# RFIDLockSCH.net
KiCad netlist of a schematic drawn in Altium Designer
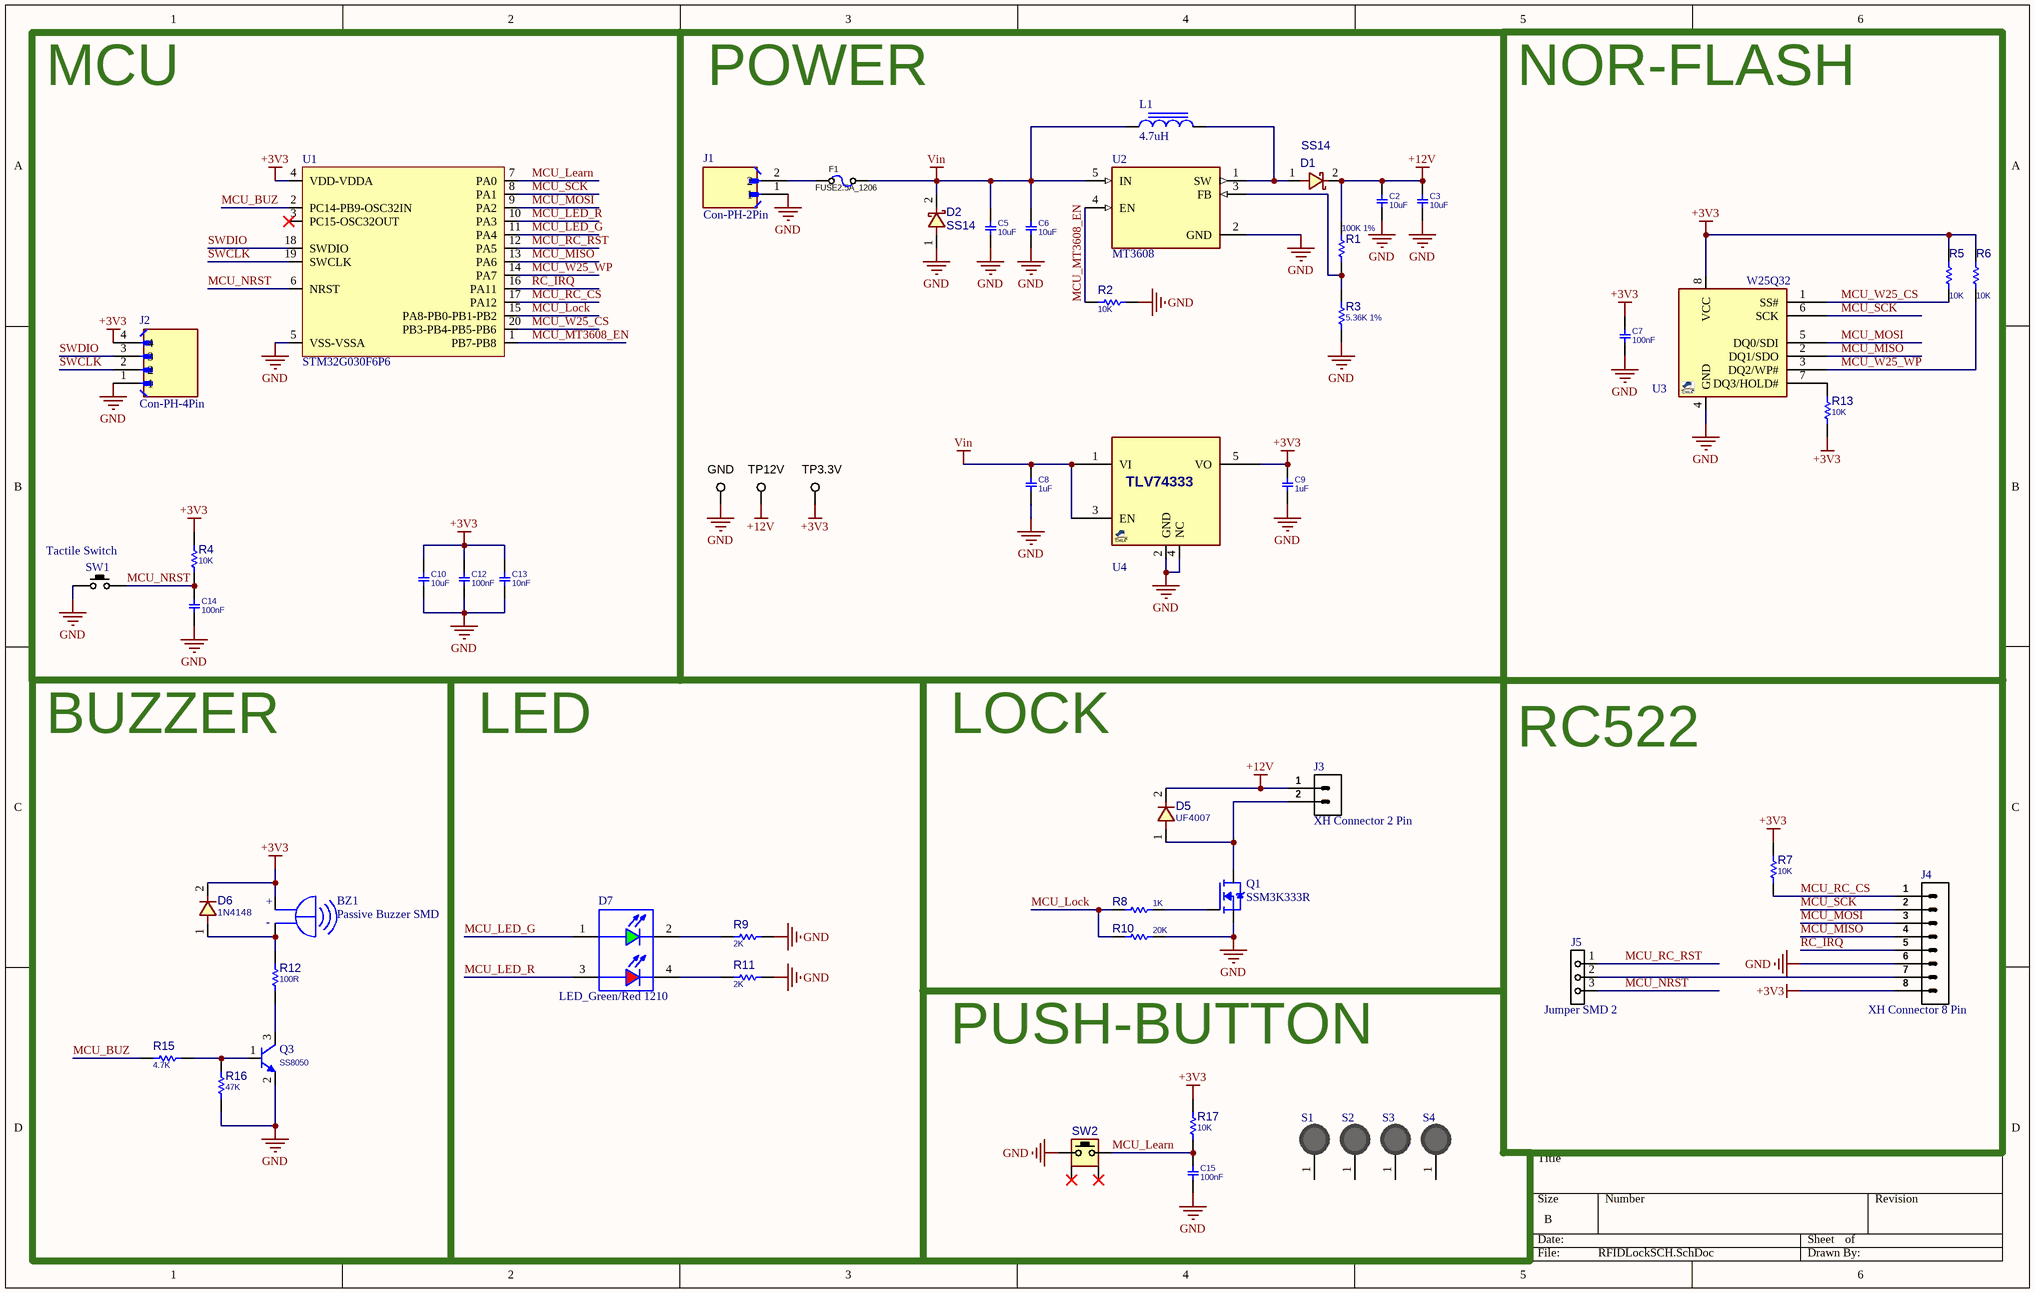
[diagram p0: RFIDLockSCH.SchDoc]

(export (version "E")
  (design (tool "Eeschema 10.0.6"))
  (components
    (comp (ref "BZ1")
      (value "Passive Buzzer SMD")
      (footprint "Passive Buzzer SMD")
      (description "Passive Buzzer 3.6V 8.5*8.5mm")
      (libsource (lib "Mehrdad") (part "Passive Buzzer SMD"))
    )
    (comp (ref "C2")
      (value "10uF")
      (footprint "C1206")
      (description "CAP, MLCC, -F, -V, MATERIAL, -%, 0201")
      (fields (field (name "MANF_P#") "MANF_PART#"))
      (libsource (lib "passive_smd") (part "CAP_SMD_MLCC_1206"))
    )
    (comp (ref "C3")
      (value "10uF")
      (footprint "C1206")
      (description "CAP, MLCC, -F, -V, MATERIAL, -%, 0201")
      (fields (field (name "MANF_P#") "MANF_PART#"))
      (libsource (lib "passive_smd") (part "CAP_SMD_MLCC_1206"))
    )
    (comp (ref "C5")
      (value "10uF")
      (footprint "C1206")
      (description "CAP, MLCC, -F, -V, MATERIAL, -%, 0201")
      (fields (field (name "MANF_P#") "MANF_PART#"))
      (libsource (lib "passive_smd") (part "CAP_SMD_MLCC_1206"))
    )
    (comp (ref "C6")
      (value "10uF")
      (footprint "C1206")
      (description "CAP, MLCC, -F, -V, MATERIAL, -%, 0201")
      (fields (field (name "MANF_P#") "MANF_PART#"))
      (libsource (lib "passive_smd") (part "CAP_SMD_MLCC_1206"))
    )
    (comp (ref "C7")
      (value "100nF")
      (footprint "C0805")
      (description "CAP, MLCC, -F, -V, MATERIAL, -%, 0201")
      (fields (field (name "MANF_P#") "MANF_PART#"))
      (libsource (lib "passive_smd") (part "CAP_SMD_MLCC_0805"))
    )
    (comp (ref "C8")
      (value "1uF")
      (footprint "C0805")
      (description "CAP, MLCC, -F, -V, MATERIAL, -%, 0201")
      (fields (field (name "MANF_P#") "MANF_PART#"))
      (libsource (lib "passive_smd") (part "CAP_SMD_MLCC_0805"))
    )
    (comp (ref "C9")
      (value "1uF")
      (footprint "C0805")
      (description "CAP, MLCC, -F, -V, MATERIAL, -%, 0201")
      (fields (field (name "MANF_P#") "MANF_PART#"))
      (libsource (lib "passive_smd") (part "CAP_SMD_MLCC_0805"))
    )
    (comp (ref "C10")
      (value "10uF")
      (footprint "C0805")
      (description "CAP, MLCC, -F, -V, MATERIAL, -%, 0201")
      (fields (field (name "MANF_P#") "MANF_PART#"))
      (libsource (lib "passive_smd") (part "CAP_SMD_MLCC_0805"))
    )
    (comp (ref "C12")
      (value "100nF")
      (footprint "C0805")
      (description "CAP, MLCC, -F, -V, MATERIAL, -%, 0201")
      (fields (field (name "MANF_P#") "MANF_PART#"))
      (libsource (lib "passive_smd") (part "CAP_SMD_MLCC_0805"))
    )
    (comp (ref "C13")
      (value "10nF")
      (footprint "C0805")
      (description "CAP, MLCC, -F, -V, MATERIAL, -%, 0201")
      (fields (field (name "MANF_P#") "MANF_PART#"))
      (libsource (lib "passive_smd") (part "CAP_SMD_MLCC_0805"))
    )
    (comp (ref "C14")
      (value "100nF")
      (footprint "C0805")
      (description "CAP, MLCC, -F, -V, MATERIAL, -%, 0201")
      (fields (field (name "MANF_P#") "MANF_PART#"))
      (libsource (lib "passive_smd") (part "CAP_SMD_MLCC_0805"))
    )
    (comp (ref "C15")
      (value "100nF")
      (footprint "C0805")
      (description "CAP, MLCC, -F, -V, MATERIAL, -%, 0201")
      (fields (field (name "MANF_P#") "MANF_PART#"))
      (libsource (lib "passive_smd") (part "CAP_SMD_MLCC_0805"))
    )
    (comp (ref "D1")
      (value "SS14")
      (footprint "D_SMA")
      (description "DIODE, SCHOTTKY, 40V, 3A")
      (fields (field (name "MANF") "DIODES") (field (name "MANF_P#") "1N5822"))
      (libsource (lib "diode") (part "DIODE_SMD_SCHOTTKY_1N5822"))
    )
    (comp (ref "D2")
      (value "SS14")
      (footprint "D_SMA")
      (description "DIODE, SCHOTTKY, 40V, 3A")
      (fields (field (name "MANF") "DIODES") (field (name "MANF_P#") "1N5822"))
      (libsource (lib "diode") (part "DIODE_SMD_SCHOTTKY_1N5822"))
    )
    (comp (ref "D5")
      (value "UF4007")
      (footprint "D_SMA")
      (description "DIODE, GENERAL PURPOSE, 50V/1A")
      (fields (field (name "MANF") "MANF") (field (name "MANF_P#") "1N4001"))
      (libsource (lib "diode") (part "DIODE_SMD_1N4001"))
    )
    (comp (ref "D6")
      (value "1N4148")
      (footprint "D_SOD123W")
      (description "DIODE, FAST SWTICHING, SMD")
      (fields (field (name "MANF") "DIODE") (field (name "MANF_P#") "1N4148W"))
      (libsource (lib "diode") (part "DIODE_SMD_1N4148_SOD123"))
    )
    (comp (ref "D7")
      (value "LED_Green/Red 1210")
      (footprint "LED_Green/Red 1210")
      (libsource (lib "Mehrdad") (part "LED_Green/Red 1210"))
    )
    (comp (ref "F1")
      (value "FUSE2.5A_1206")
      (footprint "F1206")
      (description "Fuse, 3A, 32VDC, 1206, SMD, Slow Blow")
      (fields (field (name "MANF") "Bourns") (field (name "MANF_P#") "SF-1206SP300-2"))
      (libsource (lib "protect_tvs_esd_fuse") (part "FUSE_3A_1206_SLOW"))
    )
    (comp (ref "GND")
      (value "TESTPOINT_SMD")
      (footprint "TPSMD_S1")
      (description "TEST POINT")
      (fields (field (name "MANF") "MANF") (field (name "MANF_P#") "MANF_P#"))
      (libsource (lib "test-tp_jumper") (part "TESTPOINT_SMD"))
    )
    (comp (ref "J1")
      (value "Con-PH-2Pin")
      (footprint "Con-PH-2Pin-RA")
      (description "Connector Header Through Hole 2 position 0.079 (2.00mm)")
      (libsource (lib "Mehrdad") (part "Con-PH-2Pin"))
    )
    (comp (ref "J2")
      (value "Con-PH-4Pin")
      (footprint "Con-PH-4Pin-ST")
      (description "Connector Header Through Hole 4 position 0.079 (2.00mm)")
      (libsource (lib "Mehrdad") (part "Con-PH-4Pin"))
    )
    (comp (ref "J3")
      (value "XH Connector 2 Pin")
      (footprint "XH 2 Pin - 2.5mm")
      (description "XH, 2-Pin")
      (fields (field (name "PUBLISHER") "Majid Derhambakhsh"))
      (libsource (lib "mBedLab Altium Library (2024-04-20)") (part "XH 2"))
    )
    (comp (ref "J4")
      (value "XH Connector 8 Pin")
      (footprint "XH 8 Pin - 2.5mm")
      (description "XH, 8-Pin")
      (fields (field (name "PUBLISHER") "Majid Derhambakhsh"))
      (libsource (lib "mBedLab Altium Library (2024-04-20)") (part "XH 8"))
    )
    (comp (ref "J5")
      (value "Jumper SMD 2")
      (footprint "Jumper SMD 2")
      (description "3Pin Jumper")
      (libsource (lib "Mehrdad") (part "Jumper SMD 2"))
    )
    (comp (ref "L1")
      (value "4.7uH")
      (footprint "SMD Inductor 3")
      (description "1008 (2520 metric) Part Number : DFE252012F-4R7M=P2")
      (libsource (lib "Mehrdad") (part "SMD Inductor 3"))
    )
    (comp (ref "Q1")
      (value "SSM3K333R")
      (footprint "SSM3K333R")
      (description "N-Channel 30 V 6A (Ta) 1W (Ta) Surface Mount SOT-23F")
      (libsource (lib "Mehrdad") (part "SSM3K333R"))
    )
    (comp (ref "Q3")
      (value "SS8050")
      (footprint "SOT23_3")
      (description "BJT, NPN, 25v, 1.5A, SMD, SOT23")
      (fields (field (name "MANF") "GALAXY"))
      (libsource (lib "transistor_bjt") (part "NPN_SS8050_SOT23"))
    )
    (comp (ref "R1")
      (value "100K 1%")
      (footprint "R0805")
      (description "RESISTOR, SMD")
      (libsource (lib "passive_smd") (part "RES_SMD_0805"))
    )
    (comp (ref "R2")
      (value "10K")
      (footprint "R0805")
      (description "RESISTOR, SMD")
      (libsource (lib "passive_smd") (part "RES_SMD_0805"))
    )
    (comp (ref "R3")
      (value "5.36K 1%")
      (footprint "R0805")
      (description "RESISTOR, SMD")
      (libsource (lib "passive_smd") (part "RES_SMD_0805"))
    )
    (comp (ref "R4")
      (value "10K")
      (footprint "R0805")
      (description "RESISTOR, SMD")
      (libsource (lib "passive_smd") (part "RES_SMD_0805"))
    )
    (comp (ref "R5")
      (value "10K")
      (footprint "R0805")
      (description "RESISTOR, SMD")
      (libsource (lib "passive_smd") (part "RES_SMD_0805"))
    )
    (comp (ref "R6")
      (value "10K")
      (footprint "R0805")
      (description "RESISTOR, SMD")
      (libsource (lib "passive_smd") (part "RES_SMD_0805"))
    )
    (comp (ref "R7")
      (value "10K")
      (footprint "R0805")
      (description "RESISTOR, SMD")
      (libsource (lib "passive_smd") (part "RES_SMD_0805"))
    )
    (comp (ref "R8")
      (value "1K")
      (footprint "R0805")
      (description "RESISTOR, SMD")
      (libsource (lib "passive_smd") (part "RES_SMD_0805"))
    )
    (comp (ref "R9")
      (value "2K")
      (footprint "R0805")
      (description "RESISTOR, SMD")
      (libsource (lib "passive_smd") (part "RES_SMD_0805"))
    )
    (comp (ref "R10")
      (value "20K")
      (footprint "R0805")
      (description "RESISTOR, SMD")
      (libsource (lib "passive_smd") (part "RES_SMD_0805"))
    )
    (comp (ref "R11")
      (value "2K")
      (footprint "R0805")
      (description "RESISTOR, SMD")
      (libsource (lib "passive_smd") (part "RES_SMD_0805"))
    )
    (comp (ref "R12")
      (value "100R")
      (footprint "R0805")
      (description "RESISTOR, SMD")
      (libsource (lib "passive_smd") (part "RES_SMD_0805"))
    )
    (comp (ref "R13")
      (value "10K")
      (footprint "R0805")
      (description "RESISTOR, SMD")
      (libsource (lib "passive_smd") (part "RES_SMD_0805"))
    )
    (comp (ref "R15")
      (value "4.7K")
      (footprint "R0805")
      (description "RESISTOR, SMD")
      (libsource (lib "passive_smd") (part "RES_SMD_0805"))
    )
    (comp (ref "R16")
      (value "47K")
      (footprint "R0805")
      (description "RESISTOR, SMD")
      (libsource (lib "passive_smd") (part "RES_SMD_0805"))
    )
    (comp (ref "R17")
      (value "10K")
      (footprint "R0805")
      (description "RESISTOR, SMD")
      (libsource (lib "passive_smd") (part "RES_SMD_0805"))
    )
    (comp (ref "S1")
      (value "Screw 1")
      (footprint "Screw 1")
      (description "Screw 3")
      (libsource (lib "Mehrdad") (part "Screw 1"))
    )
    (comp (ref "S2")
      (value "Screw 1")
      (footprint "Screw 1")
      (description "Screw 3")
      (libsource (lib "Mehrdad") (part "Screw 1"))
    )
    (comp (ref "S3")
      (value "Screw 1")
      (footprint "Screw 1")
      (description "Screw 3")
      (libsource (lib "Mehrdad") (part "Screw 1"))
    )
    (comp (ref "S4")
      (value "Screw 1")
      (footprint "Screw 1")
      (description "Screw 3")
      (libsource (lib "Mehrdad") (part "Screw 1"))
    )
    (comp (ref "SW1")
      (value "Tactile Switch")
      (footprint "Tactil Switch 3*4*2")
      (description "3x6x5 mm - 2 Pin")
      (libsource (lib "Mehrdad") (part "Tactile Switch"))
    )
    (comp (ref "SW2")
      (value "PUSHBUTTON")
      (footprint "SWPBT_SPST_R_6X6X10")
      (description "SWITCH, PUSH BUTTON, TACTILE, THD, SPST, RIGHT")
      (libsource (lib "switch_tact_PUSHB") (part "SWPBT_SPST_R_6X6X10"))
    )
    (comp (ref "TP3.3V")
      (value "TESTPOINT_SMD")
      (footprint "TPSMD_S1")
      (description "TEST POINT")
      (fields (field (name "MANF") "MANF") (field (name "MANF_P#") "MANF_P#"))
      (libsource (lib "test-tp_jumper") (part "TESTPOINT_SMD"))
    )
    (comp (ref "TP12V")
      (value "TESTPOINT_SMD")
      (footprint "TPSMD_S1")
      (description "TEST POINT")
      (fields (field (name "MANF") "MANF") (field (name "MANF_P#") "MANF_P#"))
      (libsource (lib "test-tp_jumper") (part "TESTPOINT_SMD"))
    )
    (comp (ref "U1")
      (value "STM32G030F6P6")
      (footprint "STM32G030F6P6")
      (description "STM32G030F6P6 . TSSOP-20 . 32KB flash . 8 KB SRAM . 17I/O . 64Mhz")
      (libsource (lib "Mehrdad") (part "STM32G030F6P6"))
    )
    (comp (ref "U2")
      (value "MT3608")
      (footprint "MT3608")
      (description "High Efficiency 1.2MHz2A Step Up Converter")
      (libsource (lib "Mehrdad") (part "MT3608"))
    )
    (comp (ref "U3")
      (value "W25Q32")
      (footprint "SO_8_W")
      (description "SPI FLASH Memory, 64Mb (8M x8), 104MHz")
      (fields (field (name "MANF") "WINBOND") (field (name "MANF_P#") "W25Q64FVSSIG"))
      (libsource (lib "memory_flash_spi") (part "W25Q64FV_SO8W"))
    )
    (comp (ref "U4")
      (value "TLV74333")
      (footprint "SOT23_5")
      (description "REG, Linear, LDO0.12V, Fixed, 300mA, VIN1.4~5.5V, VOUT1~5.5V, SOT-23-5")
      (fields (field (name "MANF") "Texas Instruments") (field (name "MANF_P#") "TLV74333PDQN"))
      (libsource (lib "pwr_reg_linear_LDO_highPSRR") (part "VREG_TLV74333_SOT23"))
    )
  )
  (nets
    (net (code "1") (name "+3V3") (class "Default")
      (node (ref "BZ1") (pin "P") (pinfunction "POS_P") (pintype "passive"))
      (node (ref "C10") (pin "2") (pinfunction "2_2") (pintype "passive"))
      (node (ref "C12") (pin "2") (pinfunction "2_2") (pintype "passive"))
      (node (ref "C13") (pin "2") (pinfunction "2_2") (pintype "passive"))
      (node (ref "C7") (pin "2") (pinfunction "2_2") (pintype "passive"))
      (node (ref "C9") (pin "2") (pinfunction "2_2") (pintype "passive"))
      (node (ref "D6") (pin "2") (pinfunction "2_2") (pintype "passive"))
      (node (ref "J2") (pin "4") (pinfunction "4_4") (pintype "passive"))
      (node (ref "J4") (pin "8") (pinfunction "8_8") (pintype "passive"))
      (node (ref "R13") (pin "1") (pinfunction "1_1") (pintype "passive"))
      (node (ref "R17") (pin "1") (pinfunction "1_1") (pintype "passive"))
      (node (ref "R4") (pin "1") (pinfunction "1_1") (pintype "passive"))
      (node (ref "R5") (pin "1") (pinfunction "1_1") (pintype "passive"))
      (node (ref "R6") (pin "1") (pinfunction "1_1") (pintype "passive"))
      (node (ref "R7") (pin "1") (pinfunction "1_1") (pintype "passive"))
      (node (ref "TP3.3V") (pin "1") (pinfunction "1_1") (pintype "passive"))
      (node (ref "U1") (pin "4") (pinfunction "VDD-VDDA_4") (pintype "power_in"))
      (node (ref "U3") (pin "8") (pinfunction "VCC_8") (pintype "passive"))
      (node (ref "U4") (pin "5") (pinfunction "VO_5") (pintype "passive"))
    )
    (net (code "2") (name "+12V") (class "Default")
      (node (ref "C2") (pin "2") (pinfunction "2_2") (pintype "passive"))
      (node (ref "C3") (pin "2") (pinfunction "2_2") (pintype "passive"))
      (node (ref "D1") (pin "2") (pinfunction "2_2") (pintype "passive"))
      (node (ref "D5") (pin "2") (pinfunction "2_2") (pintype "passive"))
      (node (ref "J3") (pin "1") (pinfunction "1_1") (pintype "passive"))
      (node (ref "R1") (pin "2") (pinfunction "2_2") (pintype "passive"))
      (node (ref "TP12V") (pin "1") (pinfunction "1_1") (pintype "passive"))
    )
    (net (code "3") (name "/MCU_BUZ") (class "Default")
      (node (ref "R15") (pin "2") (pinfunction "2_2") (pintype "passive"))
      (node (ref "U1") (pin "2") (pinfunction "PC14-PB9-OSC32IN_2") (pintype "power_in"))
    )
    (net (code "4") (name "/MCU_LED_G") (class "Default")
      (node (ref "D7") (pin "1") (pinfunction "A_1") (pintype "passive"))
      (node (ref "U1") (pin "11") (pinfunction "PA4_11") (pintype "power_in"))
    )
    (net (code "5") (name "/MCU_LED_R") (class "Default")
      (node (ref "D7") (pin "3") (pinfunction "GREEN_K_3") (pintype "passive"))
      (node (ref "U1") (pin "10") (pinfunction "PA3_10") (pintype "power_in"))
    )
    (net (code "6") (name "/MCU_Learn") (class "Default")
      (node (ref "C15") (pin "2") (pinfunction "2_2") (pintype "passive"))
      (node (ref "R17") (pin "2") (pinfunction "2_2") (pintype "passive"))
      (node (ref "SW2") (pin "2") (pinfunction "2_2") (pintype "passive"))
      (node (ref "U1") (pin "7") (pinfunction "PA0_7") (pintype "power_in"))
    )
    (net (code "7") (name "/MCU_Lock") (class "Default")
      (node (ref "R10") (pin "2") (pinfunction "2_2") (pintype "passive"))
      (node (ref "R8") (pin "1") (pinfunction "1_1") (pintype "passive"))
      (node (ref "U1") (pin "15") (pinfunction "PA8-PB0-PB1-PB2_15") (pintype "power_in"))
    )
    (net (code "8") (name "/MCU_MISO") (class "Default")
      (node (ref "J4") (pin "4") (pinfunction "4_4") (pintype "passive"))
      (node (ref "U1") (pin "13") (pinfunction "PA6_13") (pintype "power_in"))
      (node (ref "U3") (pin "2") (pinfunction "DQ1/SDO_2") (pintype "passive"))
    )
    (net (code "9") (name "/MCU_MOSI") (class "Default")
      (node (ref "J4") (pin "3") (pinfunction "3_3") (pintype "passive"))
      (node (ref "U1") (pin "9") (pinfunction "PA2_9") (pintype "power_in"))
      (node (ref "U3") (pin "5") (pinfunction "DQ0/SDI_5") (pintype "passive"))
    )
    (net (code "10") (name "/MCU_MT3608_EN") (class "Default")
      (node (ref "R2") (pin "2") (pinfunction "2_2") (pintype "passive"))
      (node (ref "U1") (pin "1") (pinfunction "PB7-PB8_1") (pintype "power_in"))
      (node (ref "U2") (pin "4") (pinfunction "EN_4") (pintype "input"))
    )
    (net (code "11") (name "/MCU_NRST") (class "Default")
      (node (ref "C14") (pin "2") (pinfunction "2_2") (pintype "passive"))
      (node (ref "J5") (pin "3") (pinfunction "3_3") (pintype "passive"))
      (node (ref "R4") (pin "2") (pinfunction "2_2") (pintype "passive"))
      (node (ref "SW1") (pin "2") (pinfunction "P3_2") (pintype "passive"))
      (node (ref "U1") (pin "6") (pinfunction "NRST_6") (pintype "power_in"))
    )
    (net (code "12") (name "/MCU_RC_CS") (class "Default")
      (node (ref "J4") (pin "1") (pinfunction "1_1") (pintype "passive"))
      (node (ref "R7") (pin "2") (pinfunction "2_2") (pintype "passive"))
      (node (ref "U1") (pin "17") (pinfunction "PA12_17") (pintype "power_in"))
    )
    (net (code "13") (name "/MCU_RC_RST") (class "Default")
      (node (ref "J5") (pin "1") (pinfunction "1_1") (pintype "passive"))
      (node (ref "U1") (pin "12") (pinfunction "PA5_12") (pintype "power_in"))
    )
    (net (code "14") (name "/MCU_SCK") (class "Default")
      (node (ref "J4") (pin "2") (pinfunction "2_2") (pintype "passive"))
      (node (ref "U1") (pin "8") (pinfunction "PA1_8") (pintype "power_in"))
      (node (ref "U3") (pin "6") (pinfunction "SCK_6") (pintype "passive"))
    )
    (net (code "15") (name "/MCU_W25_CS") (class "Default")
      (node (ref "R5") (pin "2") (pinfunction "2_2") (pintype "passive"))
      (node (ref "U1") (pin "20") (pinfunction "PB3-PB4-PB5-PB6_20") (pintype "power_in"))
      (node (ref "U3") (pin "1") (pinfunction "SS#_1") (pintype "passive"))
    )
    (net (code "16") (name "/MCU_W25_WP") (class "Default")
      (node (ref "R6") (pin "2") (pinfunction "2_2") (pintype "passive"))
      (node (ref "U1") (pin "14") (pinfunction "PA7_14") (pintype "power_in"))
      (node (ref "U3") (pin "3") (pinfunction "DQ2/WP#_3") (pintype "passive"))
    )
    (net (code "17") (name "/RC_IRQ") (class "Default")
      (node (ref "J4") (pin "5") (pinfunction "5_5") (pintype "passive"))
      (node (ref "U1") (pin "16") (pinfunction "PA11_16") (pintype "power_in"))
    )
    (net (code "18") (name "/SWCLK") (class "Default")
      (node (ref "J2") (pin "2") (pinfunction "2_2") (pintype "passive"))
      (node (ref "U1") (pin "19") (pinfunction "SWCLK_19") (pintype "power_in"))
    )
    (net (code "19") (name "/SWDIO") (class "Default")
      (node (ref "J2") (pin "3") (pinfunction "3_3") (pintype "passive"))
      (node (ref "U1") (pin "18") (pinfunction "SWDIO_18") (pintype "power_in"))
    )
    (net (code "20") (name "GND") (class "Default")
      (node (ref "C10") (pin "1") (pinfunction "1_1") (pintype "passive"))
      (node (ref "C12") (pin "1") (pinfunction "1_1") (pintype "passive"))
      (node (ref "C13") (pin "1") (pinfunction "1_1") (pintype "passive"))
      (node (ref "C14") (pin "1") (pinfunction "1_1") (pintype "passive"))
      (node (ref "C15") (pin "1") (pinfunction "1_1") (pintype "passive"))
      (node (ref "C2") (pin "1") (pinfunction "1_1") (pintype "passive"))
      (node (ref "C3") (pin "1") (pinfunction "1_1") (pintype "passive"))
      (node (ref "C5") (pin "1") (pinfunction "1_1") (pintype "passive"))
      (node (ref "C6") (pin "1") (pinfunction "1_1") (pintype "passive"))
      (node (ref "C7") (pin "1") (pinfunction "1_1") (pintype "passive"))
      (node (ref "C8") (pin "1") (pinfunction "1_1") (pintype "passive"))
      (node (ref "C9") (pin "1") (pinfunction "1_1") (pintype "passive"))
      (node (ref "D2") (pin "1") (pinfunction "1_1") (pintype "passive"))
      (node (ref "GND") (pin "1") (pinfunction "1_1") (pintype "passive"))
      (node (ref "J1") (pin "1") (pinfunction "1_1") (pintype "passive"))
      (node (ref "J2") (pin "1") (pinfunction "1_1") (pintype "passive"))
      (node (ref "J4") (pin "6") (pinfunction "6_6") (pintype "passive"))
      (node (ref "Q1") (pin "2") (pinfunction "S_2") (pintype "passive"))
      (node (ref "Q3") (pin "2") (pinfunction "E_2") (pintype "passive"))
      (node (ref "R10") (pin "1") (pinfunction "1_1") (pintype "passive"))
      (node (ref "R11") (pin "2") (pinfunction "2_2") (pintype "passive"))
      (node (ref "R16") (pin "2") (pinfunction "2_2") (pintype "passive"))
      (node (ref "R2") (pin "1") (pinfunction "1_1") (pintype "passive"))
      (node (ref "R3") (pin "1") (pinfunction "1_1") (pintype "passive"))
      (node (ref "R9") (pin "2") (pinfunction "2_2") (pintype "passive"))
      (node (ref "SW1") (pin "1") (pinfunction "P1_1") (pintype "passive"))
      (node (ref "SW2") (pin "1") (pinfunction "1_1") (pintype "passive"))
      (node (ref "U1") (pin "5") (pinfunction "VSS-VSSA_5") (pintype "power_in"))
      (node (ref "U2") (pin "2") (pinfunction "GND_2") (pintype "power_in"))
      (node (ref "U3") (pin "4") (pinfunction "GND_4") (pintype "passive"))
      (node (ref "U4") (pin "2") (pinfunction "GND_2") (pintype "passive"))
      (node (ref "U4") (pin "4") (pinfunction "NC_4") (pintype "passive"))
    )
    (net (code "21") (name "Net-(BZ1-NEG)") (class "Default")
      (node (ref "BZ1") (pin "N") (pinfunction "NEG_N") (pintype "passive"))
      (node (ref "D6") (pin "1") (pinfunction "1_1") (pintype "passive"))
      (node (ref "R12") (pin "1") (pinfunction "1_1") (pintype "passive"))
    )
    (net (code "22") (name "Net-(D7-BLUE_K)") (class "Default")
      (node (ref "D7") (pin "4") (pinfunction "BLUE_K_4") (pintype "passive"))
      (node (ref "R11") (pin "1") (pinfunction "1_1") (pintype "passive"))
    )
    (net (code "23") (name "Net-(D7-RED_K)") (class "Default")
      (node (ref "D7") (pin "2") (pinfunction "RED_K_2") (pintype "passive"))
      (node (ref "R9") (pin "1") (pinfunction "1_1") (pintype "passive"))
    )
    (net (code "24") (name "Net-(F1-Pad1)") (class "Default")
      (node (ref "F1") (pin "1") (pinfunction "1_1") (pintype "passive"))
      (node (ref "J1") (pin "2") (pinfunction "2_2") (pintype "passive"))
    )
    (net (code "25") (name "Net-(J4-Pad7)") (class "Default")
      (node (ref "J4") (pin "7") (pinfunction "7_7") (pintype "passive"))
      (node (ref "J5") (pin "2") (pinfunction "2_2") (pintype "passive"))
    )
    (net (code "26") (name "Net-(Q1-D)") (class "Default")
      (node (ref "D5") (pin "1") (pinfunction "1_1") (pintype "passive"))
      (node (ref "J3") (pin "2") (pinfunction "2_2") (pintype "passive"))
      (node (ref "Q1") (pin "3") (pinfunction "D_3") (pintype "passive"))
    )
    (net (code "27") (name "Net-(Q1-G)") (class "Default")
      (node (ref "Q1") (pin "1") (pinfunction "G_1") (pintype "passive"))
      (node (ref "R8") (pin "2") (pinfunction "2_2") (pintype "passive"))
    )
    (net (code "28") (name "Net-(Q3-B)") (class "Default")
      (node (ref "Q3") (pin "1") (pinfunction "B_1") (pintype "passive"))
      (node (ref "R15") (pin "1") (pinfunction "1_1") (pintype "passive"))
      (node (ref "R16") (pin "1") (pinfunction "1_1") (pintype "passive"))
    )
    (net (code "29") (name "Net-(Q3-C)") (class "Default")
      (node (ref "Q3") (pin "3") (pinfunction "C_3") (pintype "passive"))
      (node (ref "R12") (pin "2") (pinfunction "2_2") (pintype "passive"))
    )
    (net (code "30") (name "Net-(U2-FB)") (class "Default")
      (node (ref "R1") (pin "1") (pinfunction "1_1") (pintype "passive"))
      (node (ref "R3") (pin "2") (pinfunction "2_2") (pintype "passive"))
      (node (ref "U2") (pin "3") (pinfunction "FB_3") (pintype "input"))
    )
    (net (code "31") (name "Net-(U2-SW)") (class "Default")
      (node (ref "D1") (pin "1") (pinfunction "1_1") (pintype "passive"))
      (node (ref "L1") (pin "2") (pinfunction "2_2") (pintype "passive"))
      (node (ref "U2") (pin "1") (pinfunction "SW_1") (pintype "output"))
    )
    (net (code "32") (name "Net-(U3-DQ3{slash}HOLD#)") (class "Default")
      (node (ref "R13") (pin "2") (pinfunction "2_2") (pintype "passive"))
      (node (ref "U3") (pin "7") (pinfunction "DQ3/HOLD#_7") (pintype "passive"))
    )
    (net (code "33") (name "Vin") (class "Default")
      (node (ref "C5") (pin "2") (pinfunction "2_2") (pintype "passive"))
      (node (ref "C6") (pin "2") (pinfunction "2_2") (pintype "passive"))
      (node (ref "C8") (pin "2") (pinfunction "2_2") (pintype "passive"))
      (node (ref "D2") (pin "2") (pinfunction "2_2") (pintype "passive"))
      (node (ref "F1") (pin "2") (pinfunction "2_2") (pintype "passive"))
      (node (ref "L1") (pin "1") (pinfunction "1_1") (pintype "passive"))
      (node (ref "U2") (pin "5") (pinfunction "IN_5") (pintype "input"))
      (node (ref "U4") (pin "1") (pinfunction "VI_1") (pintype "passive"))
      (node (ref "U4") (pin "3") (pinfunction "EN_3") (pintype "passive"))
    )
    (net (code "34") (name "unconnected-(S1-Pad1)") (class "Default")
      (node (ref "S1") (pin "1") (pinfunction "1_1") (pintype "power_in"))
    )
    (net (code "35") (name "unconnected-(S2-Pad1)") (class "Default")
      (node (ref "S2") (pin "1") (pinfunction "1_1") (pintype "power_in"))
    )
    (net (code "36") (name "unconnected-(S3-Pad1)") (class "Default")
      (node (ref "S3") (pin "1") (pinfunction "1_1") (pintype "power_in"))
    )
    (net (code "37") (name "unconnected-(S4-Pad1)") (class "Default")
      (node (ref "S4") (pin "1") (pinfunction "1_1") (pintype "power_in"))
    )
    (net (code "38") (name "unconnected-(SW2-PadMH1)") (class "Default")
      (node (ref "SW2") (pin "MH1") (pinfunction "MH1_MH1") (pintype "passive+no_connect"))
    )
    (net (code "39") (name "unconnected-(SW2-PadMH2)") (class "Default")
      (node (ref "SW2") (pin "MH2") (pinfunction "MH2_MH2") (pintype "passive+no_connect"))
    )
    (net (code "40") (name "unconnected-(U1-PC15-OSC32OUT-Pad3)") (class "Default")
      (node (ref "U1") (pin "3") (pinfunction "PC15-OSC32OUT_3") (pintype "power_in+no_connect"))
    )
  )
)
